# Main.net
KiCad netlist of a schematic drawn in Altium Designer
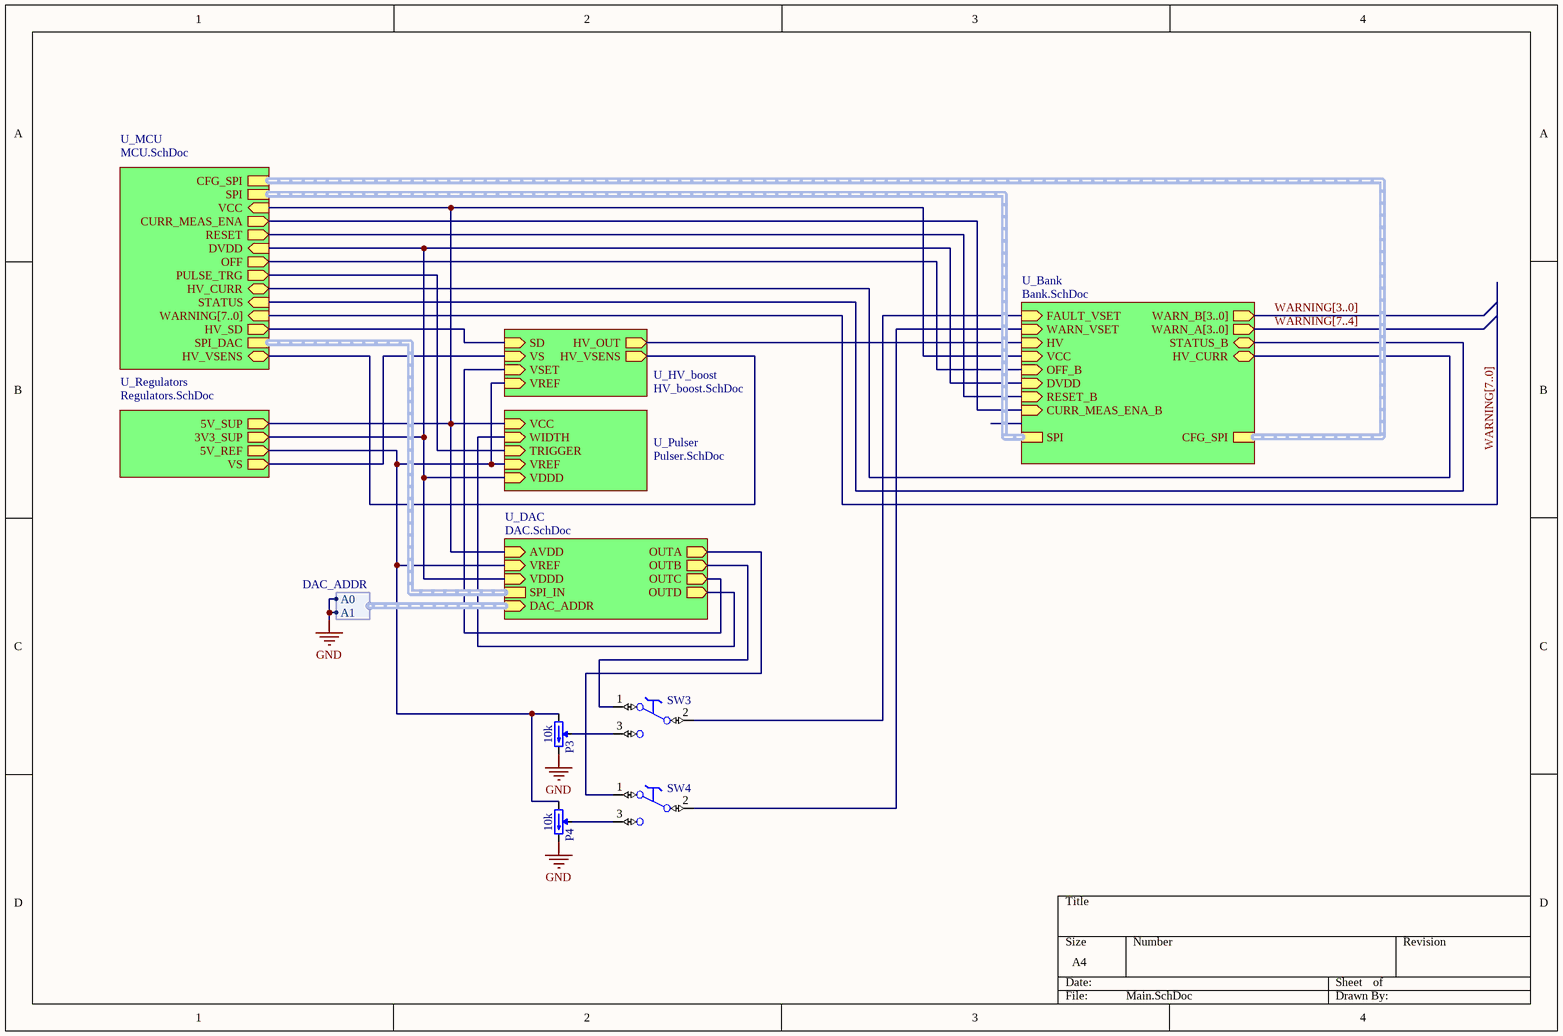
[diagram p0: Main.SchDoc]

(export (version "E")
  (design (tool "Eeschema 10.0.6"))
  (components
    (comp (ref "P3")
      (value "10k")
      (footprint "TRIM_BOURNS_3266W")
      (description "Trimming Potentiometer")
      (fields
        (field (name "PART NUMBER") "TRIM_12T_10K_BOURNS_3266W-1-103LF")
        (field (name "POWER") "0.25W")
        (field (name "AUTHOR") "CERN DEM JLC")
      )
      (libsource (lib "Resistors") (part "Trimming Potentiometer"))
    )
    (comp (ref "P4")
      (value "10k")
      (footprint "TRIM_BOURNS_3266W")
      (description "Trimming Potentiometer")
      (fields
        (field (name "PART NUMBER") "TRIM_12T_10K_BOURNS_3266W-1-103LF")
        (field (name "POWER") "0.25W")
        (field (name "AUTHOR") "CERN DEM JLC")
      )
      (libsource (lib "Resistors") (part "Trimming Potentiometer"))
    )
    (comp (ref "SW3")
      (value "Switch")
      (footprint "SW_TYCO_1-1437575-4")
      (description "SPDT Switch")
      (fields
        (field (name "PART NUMBER") "SW_TYCO_1-1437575-4")
        (field (name "MANUFACTURER") "TYCO")
        (field (name "AUTHOR") "CERN DEM JLC")
      )
      (libsource (lib "Eletro-mechanical") (part "SW SPDT 1NC-2C-3NO"))
    )
    (comp (ref "SW4")
      (value "Switch")
      (footprint "SW_TYCO_1-1437575-4")
      (description "SPDT Switch")
      (fields
        (field (name "PART NUMBER") "SW_TYCO_1-1437575-4")
        (field (name "MANUFACTURER") "TYCO")
        (field (name "AUTHOR") "CERN DEM JLC")
      )
      (libsource (lib "Eletro-mechanical") (part "SW SPDT 1NC-2C-3NO"))
    )
  )
  (nets
    (net (code "11") (name "/5V_REF") (class "Default")
      (node (ref "P3") (pin "1") (pinfunction "CCW_1") (pintype "passive"))
      (node (ref "P4") (pin "1") (pinfunction "CCW_1") (pintype "passive"))
    )
    (net (code "15") (name "/FAULT_VSET") (class "Default")
      (node (ref "SW3") (pin "2") (pinfunction "C_2") (pintype "bidirectional"))
    )
    (net (code "21") (name "/OUTA") (class "Default")
      (node (ref "SW4") (pin "1") (pinfunction "NC_1") (pintype "bidirectional"))
    )
    (net (code "22") (name "/OUTB") (class "Default")
      (node (ref "SW3") (pin "1") (pinfunction "NC_1") (pintype "bidirectional"))
    )
    (net (code "34") (name "/WARN_VSET") (class "Default")
      (node (ref "SW4") (pin "2") (pinfunction "C_2") (pintype "bidirectional"))
    )
    (net (code "36") (name "GND") (class "Default")
      (node (ref "P3") (pin "3") (pinfunction "CW_3") (pintype "passive"))
      (node (ref "P4") (pin "3") (pinfunction "CW_3") (pintype "passive"))
    )
    (net (code "37") (name "Net-(P3-W)") (class "Default")
      (node (ref "P3") (pin "2") (pinfunction "W_2") (pintype "passive"))
      (node (ref "SW3") (pin "3") (pinfunction "NO_3") (pintype "bidirectional"))
    )
    (net (code "38") (name "Net-(P4-W)") (class "Default")
      (node (ref "P4") (pin "2") (pinfunction "W_2") (pintype "passive"))
      (node (ref "SW4") (pin "3") (pinfunction "NO_3") (pintype "bidirectional"))
    )
  )
)
